# Thetis_RevG2_SCH_v1.net
KiCad netlist of a schematic drawn in EAGLE
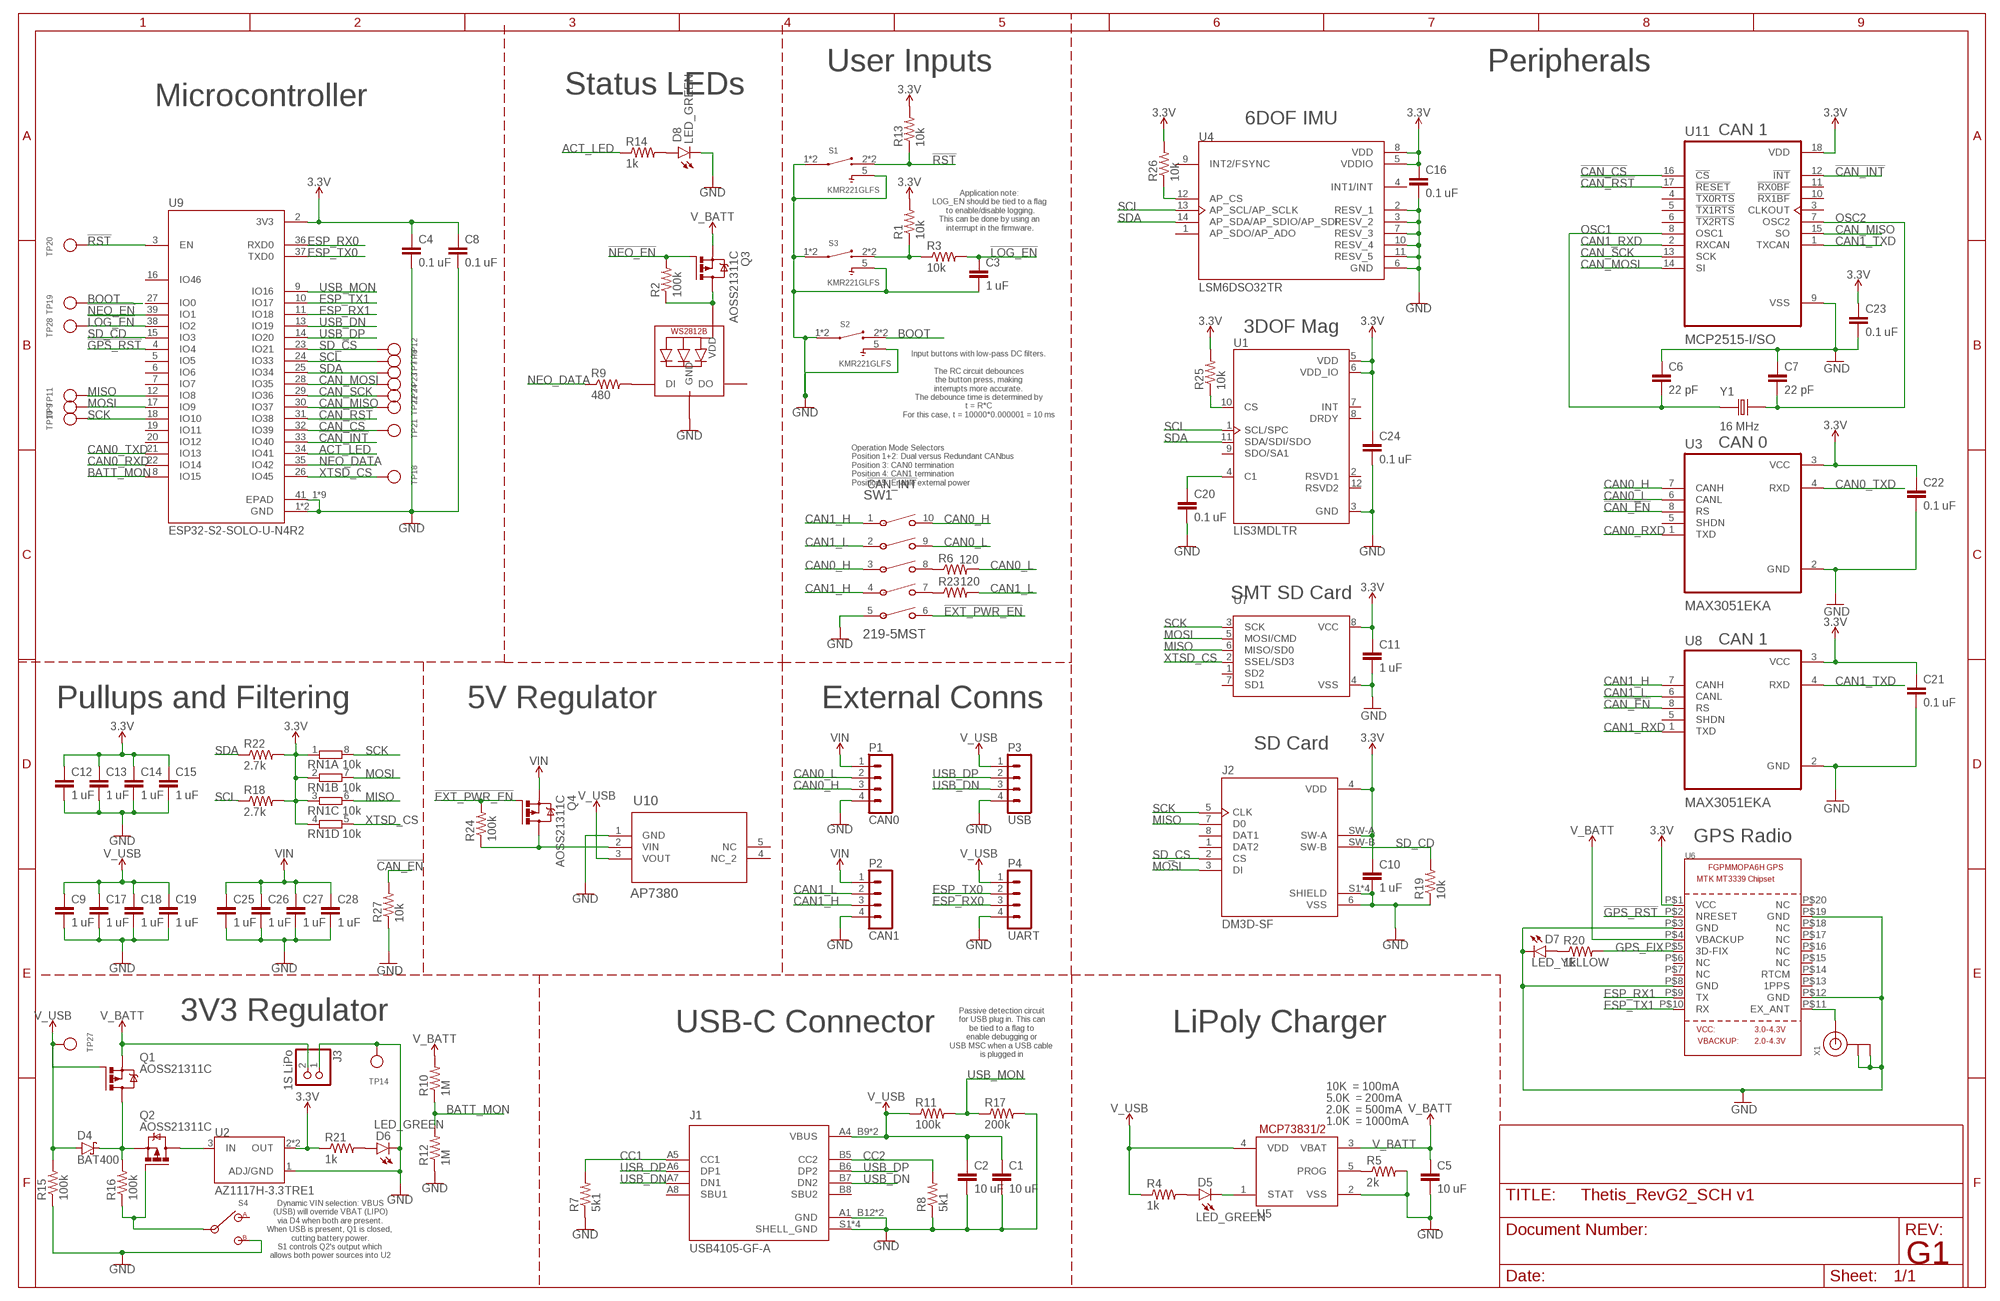
[diagram p0: schematic, sheet 1]

(export (version "E")
  (design (tool "Eeschema 10.0.6"))
  (components
    (comp (ref "C1")
      (value "10 uF")
      (footprint "eagle-import:C0603")
      (libsource (lib "eagle-import") (part "C-EUC0603"))
    )
    (comp (ref "C2")
      (value "10 uF")
      (footprint "eagle-import:C0603")
      (libsource (lib "eagle-import") (part "C-EUC0603"))
    )
    (comp (ref "C3")
      (value "1 uF")
      (footprint "eagle-import:C0603")
      (libsource (lib "eagle-import") (part "C-EUC0603"))
    )
    (comp (ref "C4")
      (value "0.1 uF")
      (footprint "eagle-import:C0603")
      (libsource (lib "eagle-import") (part "C-EUC0603"))
    )
    (comp (ref "C5")
      (value "10 uF")
      (footprint "eagle-import:C0603")
      (libsource (lib "eagle-import") (part "C-EUC0603"))
    )
    (comp (ref "C6")
      (value "22 pF")
      (footprint "eagle-import:C0603")
      (libsource (lib "eagle-import") (part "C-EUC0603"))
    )
    (comp (ref "C7")
      (value "22 pF")
      (footprint "eagle-import:C0603")
      (libsource (lib "eagle-import") (part "C-EUC0603"))
    )
    (comp (ref "C8")
      (value "0.1 uF")
      (footprint "eagle-import:C0603")
      (libsource (lib "eagle-import") (part "C-EUC0603"))
    )
    (comp (ref "C9")
      (value "1 uF")
      (footprint "eagle-import:C0603")
      (libsource (lib "eagle-import") (part "C-EUC0603"))
    )
    (comp (ref "C10")
      (value "1 uF")
      (footprint "eagle-import:C0603")
      (libsource (lib "eagle-import") (part "C-EUC0603"))
    )
    (comp (ref "C11")
      (value "1 uF")
      (footprint "eagle-import:C0603")
      (libsource (lib "eagle-import") (part "C-EUC0603"))
    )
    (comp (ref "C12")
      (value "1 uF")
      (footprint "eagle-import:C0603")
      (libsource (lib "eagle-import") (part "C-EUC0603"))
    )
    (comp (ref "C13")
      (value "1 uF")
      (footprint "eagle-import:C0603")
      (libsource (lib "eagle-import") (part "C-EUC0603"))
    )
    (comp (ref "C14")
      (value "1 uF")
      (footprint "eagle-import:C0603")
      (libsource (lib "eagle-import") (part "C-EUC0603"))
    )
    (comp (ref "C15")
      (value "1 uF")
      (footprint "eagle-import:C0603")
      (libsource (lib "eagle-import") (part "C-EUC0603"))
    )
    (comp (ref "C16")
      (value "0.1 uF")
      (footprint "eagle-import:C0603")
      (libsource (lib "eagle-import") (part "C-EUC0603"))
    )
    (comp (ref "C17")
      (value "1 uF")
      (footprint "eagle-import:C0603")
      (libsource (lib "eagle-import") (part "C-EUC0603"))
    )
    (comp (ref "C18")
      (value "1 uF")
      (footprint "eagle-import:C0603")
      (libsource (lib "eagle-import") (part "C-EUC0603"))
    )
    (comp (ref "C19")
      (value "1 uF")
      (footprint "eagle-import:C0603")
      (libsource (lib "eagle-import") (part "C-EUC0603"))
    )
    (comp (ref "C20")
      (value "0.1 uF")
      (footprint "eagle-import:C0603")
      (libsource (lib "eagle-import") (part "C-EUC0603"))
    )
    (comp (ref "C21")
      (value "0.1 uF")
      (footprint "eagle-import:C0603")
      (libsource (lib "eagle-import") (part "C-EUC0603"))
    )
    (comp (ref "C22")
      (value "0.1 uF")
      (footprint "eagle-import:C0603")
      (libsource (lib "eagle-import") (part "C-EUC0603"))
    )
    (comp (ref "C23")
      (value "0.1 uF")
      (footprint "eagle-import:C0603")
      (libsource (lib "eagle-import") (part "C-EUC0603"))
    )
    (comp (ref "C24")
      (value "0.1 uF")
      (footprint "eagle-import:C0603")
      (libsource (lib "eagle-import") (part "C-EUC0603"))
    )
    (comp (ref "C25")
      (value "1 uF")
      (footprint "eagle-import:C0603")
      (libsource (lib "eagle-import") (part "C-EUC0603"))
    )
    (comp (ref "C26")
      (value "1 uF")
      (footprint "eagle-import:C0603")
      (libsource (lib "eagle-import") (part "C-EUC0603"))
    )
    (comp (ref "C27")
      (value "1 uF")
      (footprint "eagle-import:C0603")
      (libsource (lib "eagle-import") (part "C-EUC0603"))
    )
    (comp (ref "C28")
      (value "1 uF")
      (footprint "eagle-import:C0603")
      (libsource (lib "eagle-import") (part "C-EUC0603"))
    )
    (comp (ref "D4")
      (value "BAT400")
      (footprint "eagle-import:SOT23")
      (libsource (lib "eagle-import") (part "BAS40"))
    )
    (comp (ref "D5")
      (value "LED_GREEN")
      (footprint "eagle-import:LEDC1608X65N_RND-G")
      (libsource (lib "eagle-import") (part "CHIP-ROUND-G_0603"))
    )
    (comp (ref "D6")
      (value "LED_GREEN")
      (footprint "eagle-import:LEDC1608X65N_RND-G")
      (libsource (lib "eagle-import") (part "CHIP-ROUND-G_0603"))
    )
    (comp (ref "D7")
      (value "LED_YELLOW")
      (footprint "eagle-import:LEDC1608X35N_FLAT-Y")
      (libsource (lib "eagle-import") (part "CHIP-FLAT-Y_0603-0.35MM"))
    )
    (comp (ref "D8")
      (value "LED_GREEN")
      (footprint "eagle-import:LEDC1608X65N_RND-G")
      (libsource (lib "eagle-import") (part "CHIP-ROUND-G_0603"))
    )
    (comp (ref "J1")
      (value "USB4105-GF-A")
      (footprint "eagle-import:GCT_USB4105-GF-A")
      (fields (field (name "MF") "GCT"))
      (libsource (lib "eagle-import") (part "USB4105-GF-A"))
    )
    (comp (ref "J2")
      (value "DM3D-SF")
      (footprint "eagle-import:HRS_DM3D-SF")
      (fields (field (name "MANUFACTURER") "Hirose"))
      (libsource (lib "eagle-import") (part "DM3D-SF"))
    )
    (comp (ref "J3")
      (value "1S LiPo")
      (footprint "eagle-import:JSTPH2")
      (libsource (lib "eagle-import") (part "JST_2PIN"))
    )
    (comp (ref "LED1")
      (value "WS2812B3535")
      (footprint "eagle-import:LED3535")
      (libsource (lib "eagle-import") (part "WS2812B3535"))
    )
    (comp (ref "P1")
      (value "CAN0")
      (footprint "eagle-import:B4B-PH-K")
      (libsource (lib "eagle-import") (part "B4B-PH-K"))
    )
    (comp (ref "P2")
      (value "CAN1")
      (footprint "eagle-import:B4B-PH-K")
      (libsource (lib "eagle-import") (part "B4B-PH-K"))
    )
    (comp (ref "P3")
      (value "USB")
      (footprint "eagle-import:B4B-PH-K")
      (libsource (lib "eagle-import") (part "B4B-PH-K"))
    )
    (comp (ref "P4")
      (value "UART")
      (footprint "eagle-import:B4B-PH-K")
      (libsource (lib "eagle-import") (part "B4B-PH-K"))
    )
    (comp (ref "Q1")
      (value "AOSS21311C")
      (footprint "eagle-import:SOT23")
      (fields (field (name "MANUFACTURER") "ON Semiconductor") (field (name "MPN") "BSS84"))
      (libsource (lib "eagle-import") (part "PMOSFET_BSS84"))
    )
    (comp (ref "Q2")
      (value "AOSS21311C")
      (footprint "eagle-import:SOT23")
      (fields (field (name "MANUFACTURER") "ON Semiconductor") (field (name "MPN") "BSS84"))
      (libsource (lib "eagle-import") (part "PMOSFET_BSS84"))
    )
    (comp (ref "Q3")
      (value "AOSS21311C")
      (footprint "eagle-import:SOT23")
      (fields (field (name "MANUFACTURER") "ON Semiconductor") (field (name "MPN") "BSS84"))
      (libsource (lib "eagle-import") (part "PMOSFET_BSS84"))
    )
    (comp (ref "Q4")
      (value "AOSS21311C")
      (footprint "eagle-import:SOT23")
      (fields (field (name "MANUFACTURER") "ON Semiconductor") (field (name "MPN") "BSS84"))
      (libsource (lib "eagle-import") (part "PMOSFET_BSS84"))
    )
    (comp (ref "R1")
      (value "10k")
      (footprint "eagle-import:R0603")
      (libsource (lib "eagle-import") (part "R-US_R0603"))
    )
    (comp (ref "R2")
      (value "100k")
      (footprint "eagle-import:R0603")
      (libsource (lib "eagle-import") (part "R-US_R0603"))
    )
    (comp (ref "R3")
      (value "10k")
      (footprint "eagle-import:R0603")
      (libsource (lib "eagle-import") (part "R-US_R0603"))
    )
    (comp (ref "R4")
      (value "1k")
      (footprint "eagle-import:R0603")
      (libsource (lib "eagle-import") (part "R-US_R0603"))
    )
    (comp (ref "R5")
      (value "2k")
      (footprint "eagle-import:R0603")
      (libsource (lib "eagle-import") (part "R-US_R0603"))
    )
    (comp (ref "R6")
      (value "120")
      (footprint "eagle-import:R0603")
      (libsource (lib "eagle-import") (part "R-US_R0603"))
    )
    (comp (ref "R7")
      (value "5k1")
      (footprint "eagle-import:R0603")
      (libsource (lib "eagle-import") (part "R-US_R0603"))
    )
    (comp (ref "R8")
      (value "5k1")
      (footprint "eagle-import:R0603")
      (libsource (lib "eagle-import") (part "R-US_R0603"))
    )
    (comp (ref "R9")
      (value "480")
      (footprint "eagle-import:R0603")
      (libsource (lib "eagle-import") (part "R-US_R0603"))
    )
    (comp (ref "R10")
      (value "1M")
      (footprint "eagle-import:R0603")
      (libsource (lib "eagle-import") (part "R-US_R0603"))
    )
    (comp (ref "R11")
      (value "100k")
      (footprint "eagle-import:R0603")
      (libsource (lib "eagle-import") (part "R-US_R0603"))
    )
    (comp (ref "R12")
      (value "1M")
      (footprint "eagle-import:R0603")
      (libsource (lib "eagle-import") (part "R-US_R0603"))
    )
    (comp (ref "R13")
      (value "10k")
      (footprint "eagle-import:R0603")
      (libsource (lib "eagle-import") (part "R-US_R0603"))
    )
    (comp (ref "R14")
      (value "1k")
      (footprint "eagle-import:R0603")
      (libsource (lib "eagle-import") (part "R-US_R0603"))
    )
    (comp (ref "R15")
      (value "100k")
      (footprint "eagle-import:R0603")
      (libsource (lib "eagle-import") (part "R-US_R0603"))
    )
    (comp (ref "R16")
      (value "100k")
      (footprint "eagle-import:R0603")
      (libsource (lib "eagle-import") (part "R-US_R0603"))
    )
    (comp (ref "R17")
      (value "200k")
      (footprint "eagle-import:R0603")
      (libsource (lib "eagle-import") (part "R-US_R0603"))
    )
    (comp (ref "R18")
      (value "2.7k")
      (footprint "eagle-import:R0603")
      (libsource (lib "eagle-import") (part "R-US_R0603"))
    )
    (comp (ref "R19")
      (value "10k")
      (footprint "eagle-import:R0603")
      (libsource (lib "eagle-import") (part "R-US_R0603"))
    )
    (comp (ref "R20")
      (value "1k")
      (footprint "eagle-import:R0603")
      (libsource (lib "eagle-import") (part "R-US_R0603"))
    )
    (comp (ref "R21")
      (value "1k")
      (footprint "eagle-import:R0603")
      (libsource (lib "eagle-import") (part "R-US_R0603"))
    )
    (comp (ref "R22")
      (value "2.7k")
      (footprint "eagle-import:R0603")
      (libsource (lib "eagle-import") (part "R-US_R0603"))
    )
    (comp (ref "R23")
      (value "120")
      (footprint "eagle-import:R0603")
      (libsource (lib "eagle-import") (part "R-US_R0603"))
    )
    (comp (ref "R24")
      (value "100k")
      (footprint "eagle-import:R0603")
      (libsource (lib "eagle-import") (part "R-US_R0603"))
    )
    (comp (ref "R25")
      (value "10k")
      (footprint "eagle-import:R0603")
      (libsource (lib "eagle-import") (part "R-US_R0603"))
    )
    (comp (ref "R26")
      (value "10k")
      (footprint "eagle-import:R0603")
      (libsource (lib "eagle-import") (part "R-US_R0603"))
    )
    (comp (ref "R27")
      (value "10k")
      (footprint "eagle-import:R0603")
      (libsource (lib "eagle-import") (part "R-US_R0603"))
    )
    (comp (ref "RN1")
      (value "10k")
      (footprint "eagle-import:EXBV8V")
      (libsource (lib "eagle-import") (part "4R-NEXBV8V"))
    )
    (comp (ref "S1")
      (value "KMR221GLFS")
      (footprint "eagle-import:SW_KMR221GLFS")
      (fields (field (name "MANUFACTURER") "CnK"))
      (libsource (lib "eagle-import") (part "KMR221GLFS"))
    )
    (comp (ref "S2")
      (value "KMR221GLFS")
      (footprint "eagle-import:SW_KMR221GLFS")
      (fields (field (name "MANUFACTURER") "CnK"))
      (libsource (lib "eagle-import") (part "KMR221GLFS"))
    )
    (comp (ref "S3")
      (value "KMR221GLFS")
      (footprint "eagle-import:SW_KMR221GLFS")
      (fields (field (name "MANUFACTURER") "CnK"))
      (libsource (lib "eagle-import") (part "KMR221GLFS"))
    )
    (comp (ref "S4")
      (value "CL-SB-12X")
      (footprint "eagle-import:CL-SB-12A")
      (libsource (lib "eagle-import") (part "CL-SB-12X"))
    )
    (comp (ref "SW1")
      (value "219-5MST")
      (footprint "eagle-import:SW5_219SMT")
      (fields (field (name "COPYRIGHT") "Copyright (C) 2022 Ultra Librarian. All rights reserved."))
      (libsource (lib "eagle-import") (part "219-5MSTSW5_219SMT"))
    )
    (comp (ref "TP7")
      (value "TESTPOINT1.5X2.0MM_NOCREAM")
      (footprint "eagle-import:PAD-1.5X2.0")
      (libsource (lib "eagle-import") (part "TESTPOINT1.5X2.0MM_NOCREAM"))
    )
    (comp (ref "TP8")
      (value "TESTPOINT1.5X2.0MM_NOCREAM")
      (footprint "eagle-import:PAD-1.5X2.0")
      (libsource (lib "eagle-import") (part "TESTPOINT1.5X2.0MM_NOCREAM"))
    )
    (comp (ref "TP9")
      (value "TESTPOINT1.5X2.0MM_NOCREAM")
      (footprint "eagle-import:PAD-1.5X2.0")
      (libsource (lib "eagle-import") (part "TESTPOINT1.5X2.0MM_NOCREAM"))
    )
    (comp (ref "TP10")
      (value "TESTPOINT1.5X2.0MM_NOCREAM")
      (footprint "eagle-import:PAD-1.5X2.0")
      (libsource (lib "eagle-import") (part "TESTPOINT1.5X2.0MM_NOCREAM"))
    )
    (comp (ref "TP11")
      (value "TESTPOINT1.5X2.0MM_NOCREAM")
      (footprint "eagle-import:PAD-1.5X2.0")
      (libsource (lib "eagle-import") (part "TESTPOINT1.5X2.0MM_NOCREAM"))
    )
    (comp (ref "TP12")
      (value "TESTPOINT1.5X2.0MM_NOCREAM")
      (footprint "eagle-import:PAD-1.5X2.0")
      (libsource (lib "eagle-import") (part "TESTPOINT1.5X2.0MM_NOCREAM"))
    )
    (comp (ref "TP14")
      (value "TESTPOINT1.5X2.0MM_NOCREAM")
      (footprint "eagle-import:PAD-1.5X2.0")
      (libsource (lib "eagle-import") (part "TESTPOINT1.5X2.0MM_NOCREAM"))
    )
    (comp (ref "TP18")
      (value "TESTPOINT1.5X2.0MM_NOCREAM")
      (footprint "eagle-import:PAD-1.5X2.0")
      (libsource (lib "eagle-import") (part "TESTPOINT1.5X2.0MM_NOCREAM"))
    )
    (comp (ref "TP19")
      (value "TESTPOINT1.5X2.0MM_NOCREAM")
      (footprint "eagle-import:PAD-1.5X2.0")
      (libsource (lib "eagle-import") (part "TESTPOINT1.5X2.0MM_NOCREAM"))
    )
    (comp (ref "TP20")
      (value "TESTPOINT1.5X2.0MM_NOCREAM")
      (footprint "eagle-import:PAD-1.5X2.0")
      (libsource (lib "eagle-import") (part "TESTPOINT1.5X2.0MM_NOCREAM"))
    )
    (comp (ref "TP21")
      (value "TESTPOINT1.5X2.0MM_NOCREAM")
      (footprint "eagle-import:PAD-1.5X2.0")
      (libsource (lib "eagle-import") (part "TESTPOINT1.5X2.0MM_NOCREAM"))
    )
    (comp (ref "TP22")
      (value "TESTPOINT1.5X2.0MM_NOCREAM")
      (footprint "eagle-import:PAD-1.5X2.0")
      (libsource (lib "eagle-import") (part "TESTPOINT1.5X2.0MM_NOCREAM"))
    )
    (comp (ref "TP23")
      (value "TESTPOINT1.5X2.0MM_NOCREAM")
      (footprint "eagle-import:PAD-1.5X2.0")
      (libsource (lib "eagle-import") (part "TESTPOINT1.5X2.0MM_NOCREAM"))
    )
    (comp (ref "TP24")
      (value "TESTPOINT1.5X2.0MM_NOCREAM")
      (footprint "eagle-import:PAD-1.5X2.0")
      (libsource (lib "eagle-import") (part "TESTPOINT1.5X2.0MM_NOCREAM"))
    )
    (comp (ref "TP27")
      (value "TESTPOINT1.5X2.0MM_NOCREAM")
      (footprint "eagle-import:PAD-1.5X2.0")
      (libsource (lib "eagle-import") (part "TESTPOINT1.5X2.0MM_NOCREAM"))
    )
    (comp (ref "TP28")
      (value "TESTPOINT1.5X2.0MM_NOCREAM")
      (footprint "eagle-import:PAD-1.5X2.0")
      (libsource (lib "eagle-import") (part "TESTPOINT1.5X2.0MM_NOCREAM"))
    )
    (comp (ref "U1")
      (value "LIS3MDLTR")
      (footprint "eagle-import:XDCR_LIS3MDLTR")
      (fields (field (name "MF") "STMicroelectronics"))
      (libsource (lib "eagle-import") (part "LIS3MDLTR"))
    )
    (comp (ref "U2")
      (value "AZ1117H-3.3TRE1")
      (footprint "eagle-import:SOT230P700X180-4N")
      (fields (field (name "MF") "Diodes Inc.") (field (name "MP") "AZ1117EH-5.0TRG1"))
      (libsource (lib "eagle-import") (part "AZ1117EH-5.0TRG1"))
    )
    (comp (ref "U3")
      (value "MAX3051EKA")
      (footprint "eagle-import:SOT65P280X145-8N")
      (fields
        (field (name "DIGI-KEY_PART_NUMBER") "MAX3051EKA+TTR-ND")
        (field (name "MF") "Maxim Integrated")
        (field (name "MP") "MAX3051EKA+T")
      )
      (libsource (lib "eagle-import") (part "MAX3051EKA"))
    )
    (comp (ref "U4")
      (value "LSM6DSO32TR")
      (footprint "eagle-import:PQFN50P300X250X97-14N")
      (fields (field (name "MANUFACTURER") "TDK Corporation"))
      (libsource (lib "eagle-import") (part "LSM6DSO32TR"))
    )
    (comp (ref "U5")
      (value "MCP73831/OT")
      (footprint "eagle-import:SOT23-5L")
      (libsource (lib "eagle-import") (part "MCP73831/OT"))
    )
    (comp (ref "U6")
      (value "GPS_FGPMMOPA6H")
      (footprint "eagle-import:FGPMMOPA6H")
      (libsource (lib "eagle-import") (part "GPS_FGPMMOPA6H"))
    )
    (comp (ref "U7")
      (value "SMT_SDCARD_8PIN")
      (footprint "eagle-import:LGA8_8X6")
      (libsource (lib "eagle-import") (part "SMT_SDCARD_8PIN"))
    )
    (comp (ref "U8")
      (value "MAX3051EKA")
      (footprint "eagle-import:SOT65P280X145-8N")
      (fields
        (field (name "DIGI-KEY_PART_NUMBER") "MAX3051EKA+TTR-ND")
        (field (name "MF") "Maxim Integrated")
        (field (name "MP") "MAX3051EKA+T")
      )
      (libsource (lib "eagle-import") (part "MAX3051EKA"))
    )
    (comp (ref "U9")
      (value "ESP32-S2-SOLO-U-N4R2")
      (footprint "eagle-import:XCVR_ESP32-S2-SOLO-U-N4R2")
      (fields (field (name "MANUFACTURER") "Espressif Systems"))
      (libsource (lib "eagle-import") (part "ESP32-S2-SOLO-U-N4R2"))
    )
    (comp (ref "U10")
      (value "AP7380")
      (footprint "eagle-import:SOT_50WR-7_DIO-L")
      (fields
        (field (name "MANUFACTURER_PART_NUMBER") "AP7380-50WR-7")
        (field (name "COPYRIGHT") "Copyright (C) 2022 Ultra Librarian. All rights reserved.")
      )
      (libsource (lib "eagle-import") (part "AP7380-50WR-7SOT_50WR-7_DIO-L"))
    )
    (comp (ref "U11")
      (value "MCP2515-I/SO")
      (footprint "eagle-import:SOIC127P1030X265-18N")
      (libsource (lib "eagle-import") (part "MCP2515-I/SO"))
    )
    (comp (ref "X1")
      (value "ANTENNA_U.FL")
      (footprint "eagle-import:U.FL")
      (libsource (lib "eagle-import") (part "ANTENNA_U.FL"))
    )
    (comp (ref "Y1")
      (value "16 MHz")
      (footprint "eagle-import:XTAL_ECS-160-20-3X-TR")
      (fields (field (name "MANUFACTURER") "ECS INC."))
      (libsource (lib "eagle-import") (part "ECS-160-20-3X-TR"))
    )
  )
  (nets
    (net (code "1") (name "/ACT_LED") (class "Default")
      (node (ref "R14") (pin "1") (pinfunction "1_1") (pintype "passive"))
      (node (ref "U9") (pin "34") (pinfunction "IO41_34") (pintype "bidirectional"))
    )
    (net (code "2") (name "/BATT_MON") (class "Default")
      (node (ref "R10") (pin "1") (pinfunction "1_1") (pintype "passive"))
      (node (ref "R12") (pin "2") (pinfunction "2_2") (pintype "passive"))
      (node (ref "U9") (pin "8") (pinfunction "IO15_8") (pintype "bidirectional"))
    )
    (net (code "3") (name "/BOOT") (class "Default")
      (node (ref "S2") (pin "2") (pinfunction "3_2") (pintype "passive"))
      (node (ref "S2") (pin "3") (pinfunction "3_3") (pintype "passive"))
      (node (ref "TP19") (pin "P$1") (pinfunction "P$1_P$1") (pintype "bidirectional"))
      (node (ref "U9") (pin "27") (pinfunction "IO0_27") (pintype "bidirectional"))
    )
    (net (code "4") (name "/CAN0_H") (class "Default")
      (node (ref "P1") (pin "3") (pinfunction "3_3") (pintype "passive"))
      (node (ref "SW1") (pin "10") (pinfunction "2_10") (pintype "passive"))
      (node (ref "SW1") (pin "3") (pinfunction "5_3") (pintype "passive"))
      (node (ref "U3") (pin "7") (pinfunction "CANH_7") (pintype "input"))
    )
    (net (code "5") (name "/CAN0_L") (class "Default")
      (node (ref "P1") (pin "2") (pinfunction "2_2") (pintype "passive"))
      (node (ref "R6") (pin "2") (pinfunction "2_2") (pintype "passive"))
      (node (ref "SW1") (pin "9") (pinfunction "4_9") (pintype "passive"))
      (node (ref "U3") (pin "6") (pinfunction "CANL_6") (pintype "input"))
    )
    (net (code "6") (name "/CAN0_RXD") (class "Default")
      (node (ref "U3") (pin "1") (pinfunction "TXD_1") (pintype "input"))
      (node (ref "U9") (pin "22") (pinfunction "IO14_22") (pintype "bidirectional"))
    )
    (net (code "7") (name "/CAN0_TXD") (class "Default")
      (node (ref "U3") (pin "4") (pinfunction "RXD_4") (pintype "output"))
      (node (ref "U9") (pin "21") (pinfunction "IO13_21") (pintype "bidirectional"))
    )
    (net (code "8") (name "/CAN1_H") (class "Default")
      (node (ref "P2") (pin "3") (pinfunction "3_3") (pintype "passive"))
      (node (ref "SW1") (pin "1") (pinfunction "1_1") (pintype "passive"))
      (node (ref "SW1") (pin "4") (pinfunction "7_4") (pintype "passive"))
      (node (ref "U8") (pin "7") (pinfunction "CANH_7") (pintype "input"))
    )
    (net (code "9") (name "/CAN1_L") (class "Default")
      (node (ref "P2") (pin "2") (pinfunction "2_2") (pintype "passive"))
      (node (ref "R23") (pin "2") (pinfunction "2_2") (pintype "passive"))
      (node (ref "SW1") (pin "2") (pinfunction "3_2") (pintype "passive"))
      (node (ref "U8") (pin "6") (pinfunction "CANL_6") (pintype "input"))
    )
    (net (code "10") (name "/CAN1_RXD") (class "Default")
      (node (ref "U11") (pin "2") (pinfunction "RXCAN_2") (pintype "input"))
      (node (ref "U8") (pin "1") (pinfunction "TXD_1") (pintype "input"))
    )
    (net (code "11") (name "/CAN1_TXD") (class "Default")
      (node (ref "U11") (pin "1") (pinfunction "TXCAN_1") (pintype "output"))
      (node (ref "U8") (pin "4") (pinfunction "RXD_4") (pintype "output"))
    )
    (net (code "12") (name "/CAN_MISO") (class "Default")
      (node (ref "TP22") (pin "P$1") (pinfunction "P$1_P$1") (pintype "bidirectional"))
      (node (ref "U11") (pin "15") (pinfunction "SO_15") (pintype "output"))
      (node (ref "U9") (pin "30") (pinfunction "IO37_30") (pintype "bidirectional"))
    )
    (net (code "13") (name "/CAN_MOSI") (class "Default")
      (node (ref "TP23") (pin "P$1") (pinfunction "P$1_P$1") (pintype "bidirectional"))
      (node (ref "U11") (pin "14") (pinfunction "SI_14") (pintype "input"))
      (node (ref "U9") (pin "28") (pinfunction "IO35_28") (pintype "bidirectional"))
    )
    (net (code "14") (name "/CAN_SCK") (class "Default")
      (node (ref "TP24") (pin "P$1") (pinfunction "P$1_P$1") (pintype "bidirectional"))
      (node (ref "U11") (pin "13") (pinfunction "SCK_13") (pintype "input"))
      (node (ref "U9") (pin "29") (pinfunction "IO36_29") (pintype "bidirectional"))
    )
    (net (code "15") (name "/CC1") (class "Default")
      (node (ref "J1") (pin "A5") (pinfunction "CC1_A5") (pintype "bidirectional"))
      (node (ref "R7") (pin "2") (pinfunction "2_2") (pintype "passive"))
    )
    (net (code "16") (name "/CC2") (class "Default")
      (node (ref "J1") (pin "B5") (pinfunction "CC2_B5") (pintype "bidirectional"))
      (node (ref "R8") (pin "2") (pinfunction "2_2") (pintype "passive"))
    )
    (net (code "17") (name "/ESP_RX0") (class "Default")
      (node (ref "P4") (pin "3") (pinfunction "3_3") (pintype "passive"))
      (node (ref "U9") (pin "36") (pinfunction "RXD0_36") (pintype "bidirectional"))
    )
    (net (code "18") (name "/ESP_RX1") (class "Default")
      (node (ref "U6") (pin "P$9") (pinfunction "TX_P$9") (pintype "bidirectional"))
      (node (ref "U9") (pin "11") (pinfunction "IO18_11") (pintype "bidirectional"))
    )
    (net (code "19") (name "/ESP_TX0") (class "Default")
      (node (ref "P4") (pin "2") (pinfunction "2_2") (pintype "passive"))
      (node (ref "U9") (pin "37") (pinfunction "TXD0_37") (pintype "bidirectional"))
    )
    (net (code "20") (name "/ESP_TX1") (class "Default")
      (node (ref "U6") (pin "P$10") (pinfunction "RX_P$10") (pintype "bidirectional"))
      (node (ref "U9") (pin "10") (pinfunction "IO17_10") (pintype "bidirectional"))
    )
    (net (code "21") (name "/GPS_FIX") (class "Default")
      (node (ref "R20") (pin "2") (pinfunction "2_2") (pintype "passive"))
      (node (ref "U6") (pin "P$5") (pinfunction "3D-FIX_P$5") (pintype "bidirectional"))
    )
    (net (code "22") (name "/MISO") (class "Default")
      (node (ref "J2") (pin "7") (pinfunction "D0_7") (pintype "bidirectional"))
      (node (ref "RN1") (pin "6") (pinfunction "2_6") (pintype "passive"))
      (node (ref "TP11") (pin "P$1") (pinfunction "P$1_P$1") (pintype "bidirectional"))
      (node (ref "U7") (pin "6") (pinfunction "MISO/SD0_6") (pintype "bidirectional"))
      (node (ref "U9") (pin "12") (pinfunction "IO8_12") (pintype "bidirectional"))
    )
    (net (code "23") (name "/MOSI") (class "Default")
      (node (ref "J2") (pin "3") (pinfunction "DI_3") (pintype "bidirectional"))
      (node (ref "RN1") (pin "7") (pinfunction "2_7") (pintype "passive"))
      (node (ref "TP9") (pin "P$1") (pinfunction "P$1_P$1") (pintype "bidirectional"))
      (node (ref "U7") (pin "5") (pinfunction "MOSI/CMD_5") (pintype "bidirectional"))
      (node (ref "U9") (pin "17") (pinfunction "IO9_17") (pintype "bidirectional"))
    )
    (net (code "24") (name "/NEO_DATA") (class "Default")
      (node (ref "R9") (pin "1") (pinfunction "1_1") (pintype "passive"))
      (node (ref "U9") (pin "35") (pinfunction "IO42_35") (pintype "bidirectional"))
    )
    (net (code "25") (name "/OSC1") (class "Default")
      (node (ref "C6") (pin "2") (pinfunction "2_2") (pintype "passive"))
      (node (ref "U11") (pin "8") (pinfunction "OSC1_8") (pintype "input"))
      (node (ref "Y1") (pin "1") (pinfunction "1_1") (pintype "passive"))
    )
    (net (code "26") (name "/OSC2") (class "Default")
      (node (ref "C7") (pin "2") (pinfunction "2_2") (pintype "passive"))
      (node (ref "U11") (pin "7") (pinfunction "OSC2_7") (pintype "output"))
      (node (ref "Y1") (pin "2") (pinfunction "2_2") (pintype "passive"))
    )
    (net (code "27") (name "/SCK") (class "Default")
      (node (ref "J2") (pin "5") (pinfunction "CLK_5") (pintype "bidirectional"))
      (node (ref "RN1") (pin "8") (pinfunction "2_8") (pintype "passive"))
      (node (ref "TP10") (pin "P$1") (pinfunction "P$1_P$1") (pintype "bidirectional"))
      (node (ref "U7") (pin "3") (pinfunction "SCK_3") (pintype "input"))
      (node (ref "U9") (pin "18") (pinfunction "IO10_18") (pintype "bidirectional"))
    )
    (net (code "28") (name "/SCL") (class "Default")
      (node (ref "R18") (pin "1") (pinfunction "1_1") (pintype "passive"))
      (node (ref "TP8") (pin "P$1") (pinfunction "P$1_P$1") (pintype "bidirectional"))
      (node (ref "U1") (pin "1") (pinfunction "SCL/SPC_1") (pintype "input"))
      (node (ref "U4") (pin "13") (pinfunction "AP_SCL/AP_SCLK_13") (pintype "input"))
      (node (ref "U9") (pin "24") (pinfunction "IO33_24") (pintype "bidirectional"))
    )
    (net (code "29") (name "/SDA") (class "Default")
      (node (ref "R22") (pin "1") (pinfunction "1_1") (pintype "passive"))
      (node (ref "TP7") (pin "P$1") (pinfunction "P$1_P$1") (pintype "bidirectional"))
      (node (ref "U1") (pin "11") (pinfunction "SDA/SDI/SDO_11") (pintype "bidirectional"))
      (node (ref "U4") (pin "14") (pinfunction "AP_SDA/AP_SDIO/AP_SDI_14") (pintype "bidirectional"))
      (node (ref "U9") (pin "25") (pinfunction "IO34_25") (pintype "bidirectional"))
    )
    (net (code "30") (name "/SD_CD") (class "Default")
      (node (ref "J2") (pin "SW-B") (pinfunction "SW-B_SW-B") (pintype "bidirectional"))
      (node (ref "R19") (pin "2") (pinfunction "2_2") (pintype "passive"))
      (node (ref "U9") (pin "15") (pinfunction "IO3_15") (pintype "bidirectional"))
    )
    (net (code "31") (name "/SD_CS") (class "Default")
      (node (ref "J2") (pin "2") (pinfunction "CS_2") (pintype "bidirectional"))
      (node (ref "TP12") (pin "P$1") (pinfunction "P$1_P$1") (pintype "bidirectional"))
      (node (ref "U9") (pin "23") (pinfunction "IO21_23") (pintype "bidirectional"))
    )
    (net (code "32") (name "/USB_DN") (class "Default")
      (node (ref "J1") (pin "A7") (pinfunction "DN1_A7") (pintype "bidirectional"))
      (node (ref "J1") (pin "B7") (pinfunction "DN2_B7") (pintype "bidirectional"))
      (node (ref "P3") (pin "3") (pinfunction "3_3") (pintype "passive"))
      (node (ref "U9") (pin "13") (pinfunction "IO19_13") (pintype "bidirectional"))
    )
    (net (code "33") (name "/USB_DP") (class "Default")
      (node (ref "J1") (pin "A6") (pinfunction "DP1_A6") (pintype "bidirectional"))
      (node (ref "J1") (pin "B6") (pinfunction "DP2_B6") (pintype "bidirectional"))
      (node (ref "P3") (pin "2") (pinfunction "2_2") (pintype "passive"))
      (node (ref "U9") (pin "14") (pinfunction "IO20_14") (pintype "bidirectional"))
    )
    (net (code "34") (name "/USB_MON") (class "Default")
      (node (ref "R11") (pin "2") (pinfunction "2_2") (pintype "passive"))
      (node (ref "R17") (pin "1") (pinfunction "1_1") (pintype "passive"))
      (node (ref "U9") (pin "9") (pinfunction "IO16_9") (pintype "bidirectional"))
    )
    (net (code "35") (name "/XTSD_CS") (class "Default")
      (node (ref "RN1") (pin "5") (pinfunction "2_5") (pintype "passive"))
      (node (ref "TP18") (pin "P$1") (pinfunction "P$1_P$1") (pintype "bidirectional"))
      (node (ref "U7") (pin "2") (pinfunction "SSEL/SD3_2") (pintype "bidirectional"))
      (node (ref "U9") (pin "26") (pinfunction "IO45_26") (pintype "bidirectional"))
    )
    (net (code "36") (name "/~{CAN_CS}") (class "Default")
      (node (ref "TP21") (pin "P$1") (pinfunction "P$1_P$1") (pintype "bidirectional"))
      (node (ref "U11") (pin "16") (pinfunction "~{CS}_16") (pintype "input"))
      (node (ref "U9") (pin "32") (pinfunction "IO39_32") (pintype "bidirectional"))
    )
    (net (code "37") (name "/~{CAN_EN}") (class "Default")
      (node (ref "R27") (pin "2") (pinfunction "2_2") (pintype "passive"))
      (node (ref "U3") (pin "8") (pinfunction "RS_8") (pintype "input"))
      (node (ref "U8") (pin "8") (pinfunction "RS_8") (pintype "input"))
    )
    (net (code "38") (name "/~{CAN_INT}") (class "Default")
      (node (ref "U11") (pin "12") (pinfunction "~{INT}_12") (pintype "output"))
      (node (ref "U9") (pin "33") (pinfunction "IO40_33") (pintype "bidirectional"))
    )
    (net (code "39") (name "/~{CAN_RST}") (class "Default")
      (node (ref "U11") (pin "17") (pinfunction "~{RESET}_17") (pintype "input"))
      (node (ref "U9") (pin "31") (pinfunction "IO38_31") (pintype "bidirectional"))
    )
    (net (code "40") (name "/~{EXT_PWR_EN}") (class "Default")
      (node (ref "Q4") (pin "1") (pinfunction "G_1") (pintype "passive"))
      (node (ref "R24") (pin "2") (pinfunction "2_2") (pintype "passive"))
      (node (ref "SW1") (pin "6") (pinfunction "10_6") (pintype "passive"))
    )
    (net (code "41") (name "/~{GPS_RST}") (class "Default")
      (node (ref "U6") (pin "P$2") (pinfunction "NRESET_P$2") (pintype "bidirectional"))
      (node (ref "U9") (pin "4") (pinfunction "IO4_4") (pintype "bidirectional"))
    )
    (net (code "42") (name "/~{LOG_EN}") (class "Default")
      (node (ref "C3") (pin "1") (pinfunction "1_1") (pintype "passive"))
      (node (ref "R3") (pin "2") (pinfunction "2_2") (pintype "passive"))
      (node (ref "TP28") (pin "P$1") (pinfunction "P$1_P$1") (pintype "bidirectional"))
      (node (ref "U9") (pin "38") (pinfunction "IO2_38") (pintype "bidirectional"))
    )
    (net (code "43") (name "/~{NEO_EN}") (class "Default")
      (node (ref "Q3") (pin "1") (pinfunction "G_1") (pintype "passive"))
      (node (ref "R2") (pin "2") (pinfunction "2_2") (pintype "passive"))
      (node (ref "U9") (pin "39") (pinfunction "IO1_39") (pintype "bidirectional"))
    )
    (net (code "44") (name "/~{RST}") (class "Default")
      (node (ref "R13") (pin "1") (pinfunction "1_1") (pintype "passive"))
      (node (ref "S1") (pin "2") (pinfunction "3_2") (pintype "passive"))
      (node (ref "S1") (pin "3") (pinfunction "3_3") (pintype "passive"))
      (node (ref "TP20") (pin "P$1") (pinfunction "P$1_P$1") (pintype "bidirectional"))
      (node (ref "U9") (pin "3") (pinfunction "EN_3") (pintype "input"))
    )
    (net (code "45") (name "3.3V") (class "Default")
      (node (ref "C10") (pin "1") (pinfunction "1_1") (pintype "passive"))
      (node (ref "C11") (pin "1") (pinfunction "1_1") (pintype "passive"))
      (node (ref "C12") (pin "1") (pinfunction "1_1") (pintype "passive"))
      (node (ref "C13") (pin "1") (pinfunction "1_1") (pintype "passive"))
      (node (ref "C14") (pin "1") (pinfunction "1_1") (pintype "passive"))
      (node (ref "C15") (pin "1") (pinfunction "1_1") (pintype "passive"))
      (node (ref "C16") (pin "1") (pinfunction "1_1") (pintype "passive"))
      (node (ref "C21") (pin "1") (pinfunction "1_1") (pintype "passive"))
      (node (ref "C22") (pin "1") (pinfunction "1_1") (pintype "passive"))
      (node (ref "C23") (pin "1") (pinfunction "1_1") (pintype "passive"))
      (node (ref "C24") (pin "1") (pinfunction "1_1") (pintype "passive"))
      (node (ref "C4") (pin "1") (pinfunction "1_1") (pintype "passive"))
      (node (ref "C8") (pin "1") (pinfunction "1_1") (pintype "passive"))
      (node (ref "J2") (pin "4") (pinfunction "VDD_4") (pintype "power_in"))
      (node (ref "J2") (pin "SW-A") (pinfunction "SW-A_SW-A") (pintype "bidirectional"))
      (node (ref "R1") (pin "2") (pinfunction "2_2") (pintype "passive"))
      (node (ref "R13") (pin "2") (pinfunction "2_2") (pintype "passive"))
      (node (ref "R18") (pin "2") (pinfunction "2_2") (pintype "passive"))
      (node (ref "R21") (pin "1") (pinfunction "1_1") (pintype "passive"))
      (node (ref "R22") (pin "2") (pinfunction "2_2") (pintype "passive"))
      (node (ref "R25") (pin "2") (pinfunction "2_2") (pintype "passive"))
      (node (ref "R26") (pin "2") (pinfunction "2_2") (pintype "passive"))
      (node (ref "RN1") (pin "1") (pinfunction "1_1") (pintype "passive"))
      (node (ref "RN1") (pin "2") (pinfunction "1_2") (pintype "passive"))
      (node (ref "RN1") (pin "3") (pinfunction "1_3") (pintype "passive"))
      (node (ref "RN1") (pin "4") (pinfunction "1_4") (pintype "passive"))
      (node (ref "U1") (pin "5") (pinfunction "VDD_5") (pintype "power_in"))
      (node (ref "U1") (pin "6") (pinfunction "VDD_IO_6") (pintype "power_in"))
      (node (ref "U11") (pin "18") (pinfunction "VDD_18") (pintype "power_in"))
      (node (ref "U2") (pin "2") (pinfunction "OUT_2") (pintype "output"))
      (node (ref "U2") (pin "4") (pinfunction "OUT_4") (pintype "output"))
      (node (ref "U3") (pin "3") (pinfunction "VCC_3") (pintype "power_in"))
      (node (ref "U4") (pin "5") (pinfunction "VDDIO_5") (pintype "power_in"))
      (node (ref "U4") (pin "8") (pinfunction "VDD_8") (pintype "power_in"))
      (node (ref "U6") (pin "P$1") (pinfunction "VCC_P$1") (pintype "bidirectional"))
      (node (ref "U7") (pin "8") (pinfunction "VCC_8") (pintype "power_in"))
      (node (ref "U8") (pin "3") (pinfunction "VCC_3") (pintype "power_in"))
      (node (ref "U9") (pin "2") (pinfunction "3V3_2") (pintype "power_in"))
    )
    (net (code "46") (name "GND") (class "Default")
      (node (ref "C1") (pin "2") (pinfunction "2_2") (pintype "passive"))
      (node (ref "C10") (pin "2") (pinfunction "2_2") (pintype "passive"))
      (node (ref "C11") (pin "2") (pinfunction "2_2") (pintype "passive"))
      (node (ref "C12") (pin "2") (pinfunction "2_2") (pintype "passive"))
      (node (ref "C13") (pin "2") (pinfunction "2_2") (pintype "passive"))
      (node (ref "C14") (pin "2") (pinfunction "2_2") (pintype "passive"))
      (node (ref "C15") (pin "2") (pinfunction "2_2") (pintype "passive"))
      (node (ref "C16") (pin "2") (pinfunction "2_2") (pintype "passive"))
      (node (ref "C17") (pin "2") (pinfunction "2_2") (pintype "passive"))
      (node (ref "C18") (pin "2") (pinfunction "2_2") (pintype "passive"))
      (node (ref "C19") (pin "2") (pinfunction "2_2") (pintype "passive"))
      (node (ref "C2") (pin "2") (pinfunction "2_2") (pintype "passive"))
      (node (ref "C20") (pin "2") (pinfunction "2_2") (pintype "passive"))
      (node (ref "C21") (pin "2") (pinfunction "2_2") (pintype "passive"))
      (node (ref "C22") (pin "2") (pinfunction "2_2") (pintype "passive"))
      (node (ref "C23") (pin "2") (pinfunction "2_2") (pintype "passive"))
      (node (ref "C24") (pin "2") (pinfunction "2_2") (pintype "passive"))
      (node (ref "C25") (pin "2") (pinfunction "2_2") (pintype "passive"))
      (node (ref "C26") (pin "2") (pinfunction "2_2") (pintype "passive"))
      (node (ref "C27") (pin "2") (pinfunction "2_2") (pintype "passive"))
      (node (ref "C28") (pin "2") (pinfunction "2_2") (pintype "passive"))
      (node (ref "C3") (pin "2") (pinfunction "2_2") (pintype "passive"))
      (node (ref "C4") (pin "2") (pinfunction "2_2") (pintype "passive"))
      (node (ref "C5") (pin "2") (pinfunction "2_2") (pintype "passive"))
      (node (ref "C6") (pin "1") (pinfunction "1_1") (pintype "passive"))
      (node (ref "C7") (pin "1") (pinfunction "1_1") (pintype "passive"))
      (node (ref "C8") (pin "2") (pinfunction "2_2") (pintype "passive"))
      (node (ref "C9") (pin "2") (pinfunction "2_2") (pintype "passive"))
      (node (ref "D6") (pin "C") (pinfunction "C_C") (pintype "passive"))
      (node (ref "D7") (pin "C") (pinfunction "C_C") (pintype "passive"))
      (node (ref "D8") (pin "C") (pinfunction "C_C") (pintype "passive"))
      (node (ref "J1") (pin "A1_B12") (pinfunction "GND_A1_B12") (pintype "power_in"))
      (node (ref "J1") (pin "B1_A12") (pinfunction "GND_B1_A12") (pintype "power_in"))
      (node (ref "J1") (pin "S1") (pinfunction "SHELL_GND_S1") (pintype "power_in"))
      (node (ref "J1") (pin "S2") (pinfunction "SHELL_GND_S2") (pintype "power_in"))
      (node (ref "J1") (pin "S3") (pinfunction "SHELL_GND_S3") (pintype "power_in"))
      (node (ref "J1") (pin "S4") (pinfunction "SHELL_GND_S4") (pintype "power_in"))
      (node (ref "J2") (pin "6") (pinfunction "VSS_6") (pintype "power_in"))
      (node (ref "J2") (pin "S1") (pinfunction "SHIELD_S1") (pintype "passive"))
      (node (ref "J2") (pin "S2") (pinfunction "SHIELD_S2") (pintype "passive"))
      (node (ref "J2") (pin "S3") (pinfunction "SHIELD_S3") (pintype "passive"))
      (node (ref "J2") (pin "S4") (pinfunction "SHIELD_S4") (pintype "passive"))
      (node (ref "J3") (pin "1") (pinfunction "1_1") (pintype "passive"))
      (node (ref "LED1") (pin "4") (pinfunction "GND_4") (pintype "power_in"))
      (node (ref "P1") (pin "4") (pinfunction "4_4") (pintype "passive"))
      (node (ref "P2") (pin "4") (pinfunction "4_4") (pintype "passive"))
      (node (ref "P3") (pin "4") (pinfunction "4_4") (pintype "passive"))
      (node (ref "P4") (pin "4") (pinfunction "4_4") (pintype "passive"))
      (node (ref "R12") (pin "1") (pinfunction "1_1") (pintype "passive"))
      (node (ref "R15") (pin "1") (pinfunction "1_1") (pintype "passive"))
      (node (ref "R17") (pin "2") (pinfunction "2_2") (pintype "passive"))
      (node (ref "R19") (pin "1") (pinfunction "1_1") (pintype "passive"))
      (node (ref "R27") (pin "1") (pinfunction "1_1") (pintype "passive"))
      (node (ref "R5") (pin "2") (pinfunction "2_2") (pintype "passive"))
      (node (ref "R7") (pin "1") (pinfunction "1_1") (pintype "passive"))
      (node (ref "R8") (pin "1") (pinfunction "1_1") (pintype "passive"))
      (node (ref "S1") (pin "1") (pinfunction "1_1") (pintype "passive"))
      (node (ref "S1") (pin "4") (pinfunction "1_4") (pintype "passive"))
      (node (ref "S1") (pin "5") (pinfunction "5_5") (pintype "passive"))
      (node (ref "S2") (pin "1") (pinfunction "1_1") (pintype "passive"))
      (node (ref "S2") (pin "4") (pinfunction "1_4") (pintype "passive"))
      (node (ref "S2") (pin "5") (pinfunction "5_5") (pintype "passive"))
      (node (ref "S3") (pin "1") (pinfunction "1_1") (pintype "passive"))
      (node (ref "S3") (pin "4") (pinfunction "1_4") (pintype "passive"))
      (node (ref "S3") (pin "5") (pinfunction "5_5") (pintype "passive"))
      (node (ref "S4") (pin "3") (pinfunction "3_3") (pintype "bidirectional"))
      (node (ref "SW1") (pin "5") (pinfunction "9_5") (pintype "passive"))
      (node (ref "TP14") (pin "P$1") (pinfunction "P$1_P$1") (pintype "bidirectional"))
      (node (ref "U1") (pin "3") (pinfunction "GND_3") (pintype "power_in"))
      (node (ref "U10") (pin "1") (pinfunction "GND_1") (pintype "passive"))
      (node (ref "U11") (pin "9") (pinfunction "VSS_9") (pintype "power_in"))
      (node (ref "U2") (pin "1") (pinfunction "ADJ/GND_1") (pintype "power_in"))
      (node (ref "U3") (pin "2") (pinfunction "GND_2") (pintype "power_in"))
      (node (ref "U4") (pin "10") (pinfunction "RESV_4_10") (pintype "bidirectional"))
      (node (ref "U4") (pin "11") (pinfunction "RESV_5_11") (pintype "bidirectional"))
      (node (ref "U4") (pin "2") (pinfunction "RESV_1_2") (pintype "bidirectional"))
      (node (ref "U4") (pin "3") (pinfunction "RESV_2_3") (pintype "bidirectional"))
      (node (ref "U4") (pin "6") (pinfunction "GND_6") (pintype "power_in"))
      (node (ref "U4") (pin "7") (pinfunction "RESV_3_7") (pintype "bidirectional"))
      (node (ref "U5") (pin "2") (pinfunction "VSS_2") (pintype "power_in"))
      (node (ref "U6") (pin "P$12") (pinfunction "GND_P$12") (pintype "bidirectional"))
      (node (ref "U6") (pin "P$19") (pinfunction "GND_P$19") (pintype "bidirectional"))
      (node (ref "U6") (pin "P$3") (pinfunction "GND_P$3") (pintype "bidirectional"))
      (node (ref "U6") (pin "P$8") (pinfunction "GND_P$8") (pintype "bidirectional"))
      (node (ref "U7") (pin "4") (pinfunction "VSS_4") (pintype "power_in"))
      (node (ref "U8") (pin "2") (pinfunction "GND_2") (pintype "power_in"))
      (node (ref "U9") (pin "1") (pinfunction "GND_1") (pintype "power_in"))
      (node (ref "U9") (pin "40") (pinfunction "GND_40") (pintype "power_in"))
      (node (ref "U9") (pin "41_1") (pinfunction "EPAD_41_1") (pintype "power_in"))
      (node (ref "U9") (pin "41_2") (pinfunction "EPAD_41_2") (pintype "power_in"))
      (node (ref "U9") (pin "41_3") (pinfunction "EPAD_41_3") (pintype "power_in"))
      (node (ref "U9") (pin "41_4") (pinfunction "EPAD_41_4") (pintype "power_in"))
      (node (ref "U9") (pin "41_5") (pinfunction "EPAD_41_5") (pintype "power_in"))
      (node (ref "U9") (pin "41_6") (pinfunction "EPAD_41_6") (pintype "power_in"))
      (node (ref "U9") (pin "41_7") (pinfunction "EPAD_41_7") (pintype "power_in"))
      (node (ref "U9") (pin "41_8") (pinfunction "EPAD_41_8") (pintype "power_in"))
      (node (ref "U9") (pin "41_9") (pinfunction "EPAD_41_9") (pintype "power_in"))
      (node (ref "X1") (pin "1") (pinfunction "GND_1") (pintype "passive"))
      (node (ref "X1") (pin "2") (pinfunction "GND_2") (pintype "passive"))
    )
    (net (code "47") (name "Net-(D4-C)") (class "Default")
      (node (ref "D4") (pin "3") (pinfunction "C_3") (pintype "passive"))
      (node (ref "Q1") (pin "3") (pinfunction "D_3") (pintype "passive"))
      (node (ref "Q2") (pin "2") (pinfunction "S_2") (pintype "passive"))
      (node (ref "R16") (pin "2") (pinfunction "2_2") (pintype "passive"))
    )
    (net (code "48") (name "Net-(D5-PadA)") (class "Default")
      (node (ref "D5") (pin "A") (pinfunction "A_A") (pintype "passive"))
      (node (ref "R4") (pin "2") (pinfunction "2_2") (pintype "passive"))
    )
    (net (code "49") (name "Net-(D6-PadA)") (class "Default")
      (node (ref "D6") (pin "A") (pinfunction "A_A") (pintype "passive"))
      (node (ref "R21") (pin "2") (pinfunction "2_2") (pintype "passive"))
    )
    (net (code "50") (name "Net-(D7-PadA)") (class "Default")
      (node (ref "D7") (pin "A") (pinfunction "A_A") (pintype "passive"))
      (node (ref "R20") (pin "1") (pinfunction "1_1") (pintype "passive"))
    )
    (net (code "51") (name "Net-(D8-PadA)") (class "Default")
      (node (ref "D8") (pin "A") (pinfunction "A_A") (pintype "passive"))
      (node (ref "R14") (pin "2") (pinfunction "2_2") (pintype "passive"))
    )
    (net (code "52") (name "Net-(LED1-DI)") (class "Default")
      (node (ref "LED1") (pin "1") (pinfunction "DI_1") (pintype "input"))
      (node (ref "R9") (pin "2") (pinfunction "2_2") (pintype "passive"))
    )
    (net (code "53") (name "Net-(LED1-VDD)") (class "Default")
      (node (ref "LED1") (pin "2") (pinfunction "VDD_2") (pintype "power_in"))
      (node (ref "Q3") (pin "3") (pinfunction "D_3") (pintype "passive"))
      (node (ref "R2") (pin "1") (pinfunction "1_1") (pintype "passive"))
    )
    (net (code "54") (name "Net-(Q2-D)") (class "Default")
      (node (ref "Q2") (pin "3") (pinfunction "D_3") (pintype "passive"))
      (node (ref "U2") (pin "3") (pinfunction "IN_3") (pintype "input"))
    )
    (net (code "55") (name "Net-(Q2-G)") (class "Default")
      (node (ref "Q2") (pin "1") (pinfunction "G_1") (pintype "passive"))
      (node (ref "R16") (pin "1") (pinfunction "1_1") (pintype "passive"))
      (node (ref "S4") (pin "2") (pinfunction "2_2") (pintype "bidirectional"))
    )
    (net (code "56") (name "Net-(Q4-D)") (class "Default")
      (node (ref "Q4") (pin "3") (pinfunction "D_3") (pintype "passive"))
      (node (ref "R24") (pin "1") (pinfunction "1_1") (pintype "passive"))
      (node (ref "U10") (pin "2") (pinfunction "VIN_2") (pintype "passive"))
    )
    (net (code "57") (name "Net-(R1-Pad1)") (class "Default")
      (node (ref "R1") (pin "1") (pinfunction "1_1") (pintype "passive"))
      (node (ref "R3") (pin "1") (pinfunction "1_1") (pintype "passive"))
      (node (ref "S3") (pin "2") (pinfunction "3_2") (pintype "passive"))
      (node (ref "S3") (pin "3") (pinfunction "3_3") (pintype "passive"))
    )
    (net (code "58") (name "Net-(SW1-6)") (class "Default")
      (node (ref "R6") (pin "1") (pinfunction "1_1") (pintype "passive"))
      (node (ref "SW1") (pin "8") (pinfunction "6_8") (pintype "passive"))
    )
    (net (code "59") (name "Net-(SW1-8)") (class "Default")
      (node (ref "R23") (pin "1") (pinfunction "1_1") (pintype "passive"))
      (node (ref "SW1") (pin "7") (pinfunction "8_7") (pintype "passive"))
    )
    (net (code "60") (name "Net-(U1-C1)") (class "Default")
      (node (ref "C20") (pin "1") (pinfunction "1_1") (pintype "passive"))
      (node (ref "U1") (pin "4") (pinfunction "C1_4") (pintype "passive"))
    )
    (net (code "61") (name "Net-(U1-CS)") (class "Default")
      (node (ref "R25") (pin "1") (pinfunction "1_1") (pintype "passive"))
      (node (ref "U1") (pin "10") (pinfunction "CS_10") (pintype "input"))
    )
    (net (code "62") (name "Net-(U4-AP_CS)") (class "Default")
      (node (ref "R26") (pin "1") (pinfunction "1_1") (pintype "passive"))
      (node (ref "U4") (pin "12") (pinfunction "AP_CS_12") (pintype "input"))
    )
    (net (code "63") (name "Net-(U5-PROG)") (class "Default")
      (node (ref "R5") (pin "1") (pinfunction "1_1") (pintype "passive"))
      (node (ref "U5") (pin "5") (pinfunction "PROG_5") (pintype "input"))
    )
    (net (code "64") (name "Net-(U5-STAT)") (class "Default")
      (node (ref "D5") (pin "C") (pinfunction "C_C") (pintype "passive"))
      (node (ref "U5") (pin "1") (pinfunction "STAT_1") (pintype "output"))
    )
    (net (code "65") (name "Net-(U6-EX_ANT)") (class "Default")
      (node (ref "U6") (pin "P$11") (pinfunction "EX_ANT_P$11") (pintype "bidirectional"))
      (node (ref "X1") (pin "3") (pinfunction "SIGNAL_3") (pintype "passive"))
    )
    (net (code "66") (name "VIN") (class "Default")
      (node (ref "C25") (pin "1") (pinfunction "1_1") (pintype "passive"))
      (node (ref "C26") (pin "1") (pinfunction "1_1") (pintype "passive"))
      (node (ref "C27") (pin "1") (pinfunction "1_1") (pintype "passive"))
      (node (ref "C28") (pin "1") (pinfunction "1_1") (pintype "passive"))
      (node (ref "P1") (pin "1") (pinfunction "1_1") (pintype "passive"))
      (node (ref "P2") (pin "1") (pinfunction "1_1") (pintype "passive"))
      (node (ref "Q4") (pin "2") (pinfunction "S_2") (pintype "passive"))
    )
    (net (code "67") (name "V_BATT") (class "Default")
      (node (ref "C5") (pin "1") (pinfunction "1_1") (pintype "passive"))
      (node (ref "J3") (pin "2") (pinfunction "2_2") (pintype "passive"))
      (node (ref "Q1") (pin "2") (pinfunction "S_2") (pintype "passive"))
      (node (ref "Q3") (pin "2") (pinfunction "S_2") (pintype "passive"))
      (node (ref "R10") (pin "2") (pinfunction "2_2") (pintype "passive"))
      (node (ref "U5") (pin "3") (pinfunction "VBAT_3") (pintype "bidirectional"))
      (node (ref "U6") (pin "P$4") (pinfunction "VBACKUP_P$4") (pintype "bidirectional"))
    )
    (net (code "68") (name "V_USB") (class "Default")
      (node (ref "C1") (pin "1") (pinfunction "1_1") (pintype "passive"))
      (node (ref "C17") (pin "1") (pinfunction "1_1") (pintype "passive"))
      (node (ref "C18") (pin "1") (pinfunction "1_1") (pintype "passive"))
      (node (ref "C19") (pin "1") (pinfunction "1_1") (pintype "passive"))
      (node (ref "C2") (pin "1") (pinfunction "1_1") (pintype "passive"))
      (node (ref "C9") (pin "1") (pinfunction "1_1") (pintype "passive"))
      (node (ref "D4") (pin "1") (pinfunction "A_1") (pintype "passive"))
      (node (ref "J1") (pin "A4_B9") (pinfunction "VBUS_A4_B9") (pintype "power_in"))
      (node (ref "J1") (pin "B4_A9") (pinfunction "VBUS_B4_A9") (pintype "power_in"))
      (node (ref "P3") (pin "1") (pinfunction "1_1") (pintype "passive"))
      (node (ref "P4") (pin "1") (pinfunction "1_1") (pintype "passive"))
      (node (ref "Q1") (pin "1") (pinfunction "G_1") (pintype "passive"))
      (node (ref "R11") (pin "1") (pinfunction "1_1") (pintype "passive"))
      (node (ref "R15") (pin "2") (pinfunction "2_2") (pintype "passive"))
      (node (ref "R4") (pin "1") (pinfunction "1_1") (pintype "passive"))
      (node (ref "TP27") (pin "P$1") (pinfunction "P$1_P$1") (pintype "bidirectional"))
      (node (ref "U10") (pin "3") (pinfunction "VOUT_3") (pintype "output"))
      (node (ref "U5") (pin "4") (pinfunction "VDD_4") (pintype "power_in"))
    )
    (net (code "69") (name "unconnected-(J1-SBU1-PadA8)") (class "Default")
      (node (ref "J1") (pin "A8") (pinfunction "SBU1_A8") (pintype "bidirectional"))
    )
    (net (code "70") (name "unconnected-(J1-SBU2-PadB8)") (class "Default")
      (node (ref "J1") (pin "B8") (pinfunction "SBU2_B8") (pintype "bidirectional"))
    )
    (net (code "71") (name "unconnected-(J2-DAT1-Pad8)") (class "Default")
      (node (ref "J2") (pin "8") (pinfunction "DAT1_8") (pintype "bidirectional"))
    )
    (net (code "72") (name "unconnected-(J2-DAT2-Pad1)") (class "Default")
      (node (ref "J2") (pin "1") (pinfunction "DAT2_1") (pintype "bidirectional"))
    )
    (net (code "73") (name "unconnected-(LED1-DO-Pad3)") (class "Default")
      (node (ref "LED1") (pin "3") (pinfunction "DO_3") (pintype "output"))
    )
    (net (code "74") (name "unconnected-(S4-Pad1)") (class "Default")
      (node (ref "S4") (pin "1") (pinfunction "1_1") (pintype "bidirectional"))
    )
    (net (code "75") (name "unconnected-(U1-DRDY-Pad8)") (class "Default")
      (node (ref "U1") (pin "8") (pinfunction "DRDY_8") (pintype "output"))
    )
    (net (code "76") (name "unconnected-(U1-INT-Pad7)") (class "Default")
      (node (ref "U1") (pin "7") (pinfunction "INT_7") (pintype "output"))
    )
    (net (code "77") (name "unconnected-(U1-RSVD1-Pad2)") (class "Default")
      (node (ref "U1") (pin "2") (pinfunction "RSVD1_2") (pintype "passive"))
    )
    (net (code "78") (name "unconnected-(U1-RSVD2-Pad12)") (class "Default")
      (node (ref "U1") (pin "12") (pinfunction "RSVD2_12") (pintype "passive"))
    )
    (net (code "79") (name "unconnected-(U1-SDO{slash}SA1-Pad9)") (class "Default")
      (node (ref "U1") (pin "9") (pinfunction "SDO/SA1_9") (pintype "bidirectional"))
    )
    (net (code "80") (name "unconnected-(U3-SHDN-Pad5)") (class "Default")
      (node (ref "U3") (pin "5") (pinfunction "SHDN_5") (pintype "input"))
    )
    (net (code "81") (name "unconnected-(U4-AP_SDO{slash}AP_ADO-Pad1)") (class "Default")
      (node (ref "U4") (pin "1") (pinfunction "AP_SDO/AP_ADO_1") (pintype "output"))
    )
    (net (code "82") (name "unconnected-(U4-INT1{slash}INT-Pad4)") (class "Default")
      (node (ref "U4") (pin "4") (pinfunction "INT1/INT_4") (pintype "output"))
    )
    (net (code "83") (name "unconnected-(U4-INT2{slash}FSYNC-Pad9)") (class "Default")
      (node (ref "U4") (pin "9") (pinfunction "INT2/FSYNC_9") (pintype "bidirectional"))
    )
    (net (code "84") (name "unconnected-(U6-1PPS-PadP$13)") (class "Default")
      (node (ref "U6") (pin "P$13") (pinfunction "1PPS_P$13") (pintype "bidirectional"))
    )
    (net (code "85") (name "unconnected-(U6-NC-PadP$6)") (class "Default")
      (node (ref "U6") (pin "P$6") (pinfunction "NC_P$6") (pintype "bidirectional"))
    )
    (net (code "86") (name "unconnected-(U6-NC-PadP$7)") (class "Default")
      (node (ref "U6") (pin "P$7") (pinfunction "NC_P$7") (pintype "bidirectional"))
    )
    (net (code "87") (name "unconnected-(U6-NC-PadP$15)") (class "Default")
      (node (ref "U6") (pin "P$15") (pinfunction "NC_P$15") (pintype "bidirectional"))
    )
    (net (code "88") (name "unconnected-(U6-NC-PadP$16)") (class "Default")
      (node (ref "U6") (pin "P$16") (pinfunction "NC_P$16") (pintype "bidirectional"))
    )
    (net (code "89") (name "unconnected-(U6-NC-PadP$17)") (class "Default")
      (node (ref "U6") (pin "P$17") (pinfunction "NC_P$17") (pintype "bidirectional"))
    )
    (net (code "90") (name "unconnected-(U6-NC-PadP$18)") (class "Default")
      (node (ref "U6") (pin "P$18") (pinfunction "NC_P$18") (pintype "bidirectional"))
    )
    (net (code "91") (name "unconnected-(U6-NC-PadP$20)") (class "Default")
      (node (ref "U6") (pin "P$20") (pinfunction "NC_P$20") (pintype "bidirectional"))
    )
    (net (code "92") (name "unconnected-(U6-RTCM-PadP$14)") (class "Default")
      (node (ref "U6") (pin "P$14") (pinfunction "RTCM_P$14") (pintype "bidirectional"))
    )
    (net (code "93") (name "unconnected-(U7-SD1-Pad7)") (class "Default")
      (node (ref "U7") (pin "7") (pinfunction "SD1_7") (pintype "bidirectional"))
    )
    (net (code "94") (name "unconnected-(U7-SD2-Pad1)") (class "Default")
      (node (ref "U7") (pin "1") (pinfunction "SD2_1") (pintype "bidirectional"))
    )
    (net (code "95") (name "unconnected-(U8-SHDN-Pad5)") (class "Default")
      (node (ref "U8") (pin "5") (pinfunction "SHDN_5") (pintype "input"))
    )
    (net (code "96") (name "unconnected-(U9-IO5-Pad5)") (class "Default")
      (node (ref "U9") (pin "5") (pinfunction "IO5_5") (pintype "bidirectional"))
    )
    (net (code "97") (name "unconnected-(U9-IO6-Pad6)") (class "Default")
      (node (ref "U9") (pin "6") (pinfunction "IO6_6") (pintype "bidirectional"))
    )
    (net (code "98") (name "unconnected-(U9-IO7-Pad7)") (class "Default")
      (node (ref "U9") (pin "7") (pinfunction "IO7_7") (pintype "bidirectional"))
    )
    (net (code "99") (name "unconnected-(U9-IO11-Pad19)") (class "Default")
      (node (ref "U9") (pin "19") (pinfunction "IO11_19") (pintype "bidirectional"))
    )
    (net (code "100") (name "unconnected-(U9-IO12-Pad20)") (class "Default")
      (node (ref "U9") (pin "20") (pinfunction "IO12_20") (pintype "bidirectional"))
    )
    (net (code "101") (name "unconnected-(U9-IO46-Pad16)") (class "Default")
      (node (ref "U9") (pin "16") (pinfunction "IO46_16") (pintype "input"))
    )
    (net (code "102") (name "unconnected-(U10-NC-Pad5)") (class "Default")
      (node (ref "U10") (pin "5") (pinfunction "NC_5") (pintype "no_connect"))
    )
    (net (code "103") (name "unconnected-(U10-NC_2-Pad4)") (class "Default")
      (node (ref "U10") (pin "4") (pinfunction "NC_2_4") (pintype "no_connect"))
    )
    (net (code "104") (name "unconnected-(U11-CLKOUT-Pad3)") (class "Default")
      (node (ref "U11") (pin "3") (pinfunction "CLKOUT_3") (pintype "output"))
    )
    (net (code "105") (name "unconnected-(U11-~{RX0BF}-Pad11)") (class "Default")
      (node (ref "U11") (pin "11") (pinfunction "~{RX0BF}_11") (pintype "output"))
    )
    (net (code "106") (name "unconnected-(U11-~{RX1BF}-Pad10)") (class "Default")
      (node (ref "U11") (pin "10") (pinfunction "~{RX1BF}_10") (pintype "output"))
    )
    (net (code "107") (name "unconnected-(U11-~{TX0RTS}-Pad4)") (class "Default")
      (node (ref "U11") (pin "4") (pinfunction "~{TX0RTS}_4") (pintype "input"))
    )
    (net (code "108") (name "unconnected-(U11-~{TX1RTS}-Pad5)") (class "Default")
      (node (ref "U11") (pin "5") (pinfunction "~{TX1RTS}_5") (pintype "input"))
    )
    (net (code "109") (name "unconnected-(U11-~{TX2RTS}-Pad6)") (class "Default")
      (node (ref "U11") (pin "6") (pinfunction "~{TX2RTS}_6") (pintype "input"))
    )
  )
)
